# Battery_Pack_BP8.net
KiCad netlist of a schematic drawn in Altium Designer
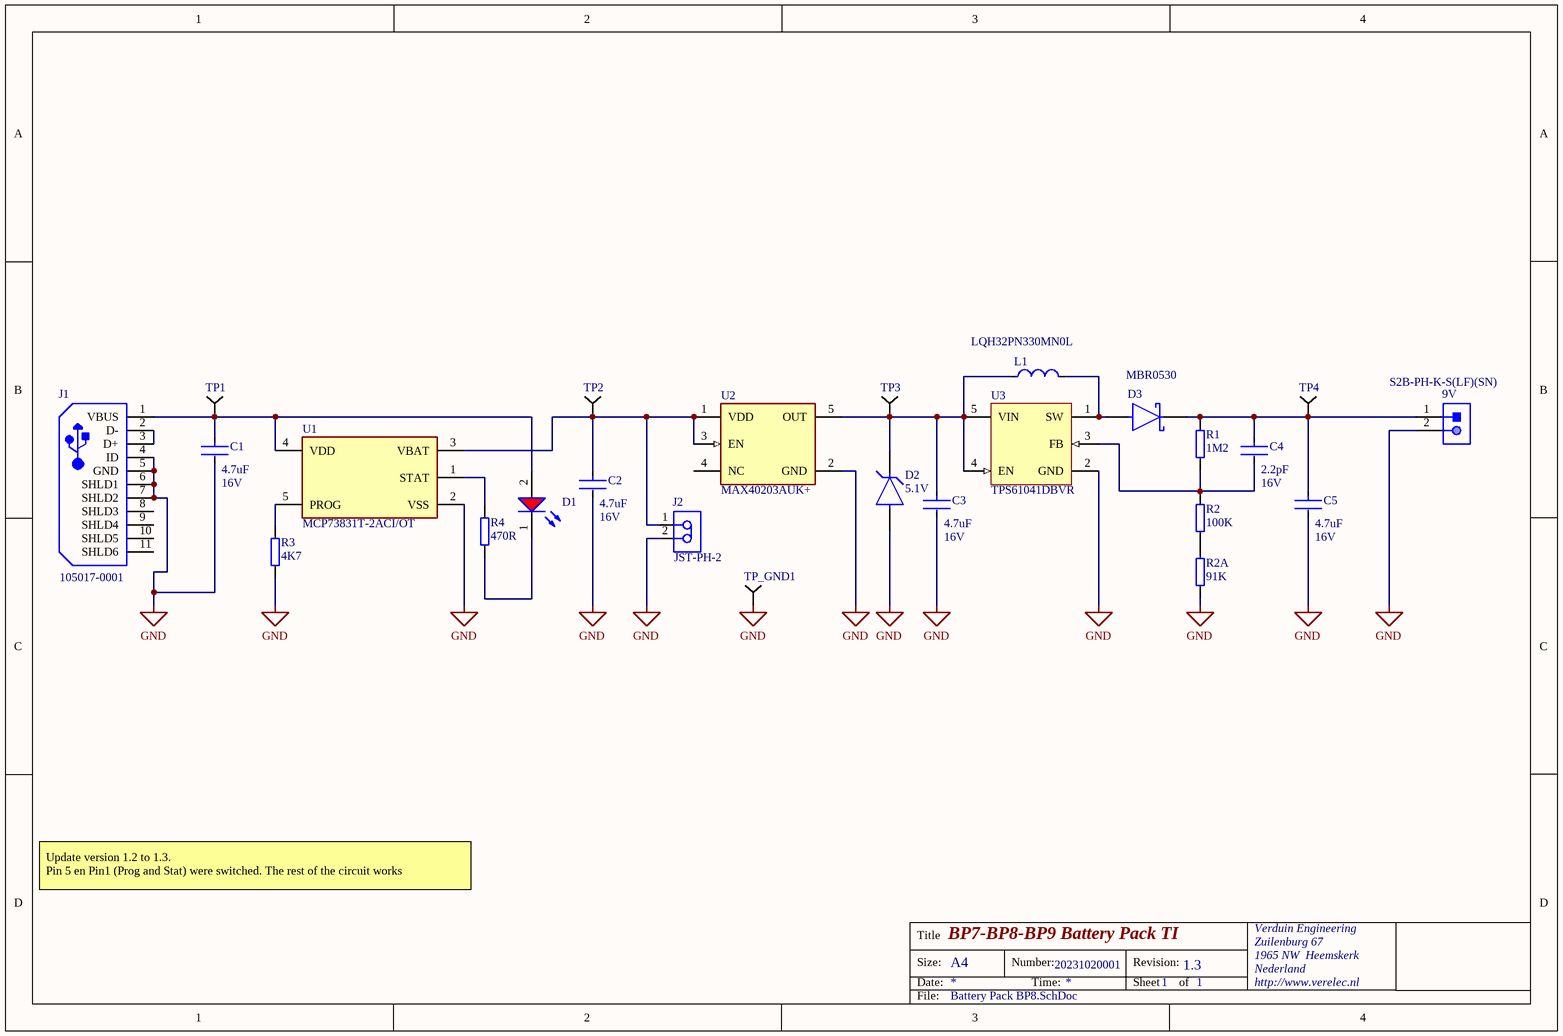
[diagram p0: Battery Pack BP8.SchDoc]

(export (version "E")
  (design (tool "Eeschema 10.0.6"))
  (components
    (comp (ref "9V")
      (value "S2B-PH-K-S(LF)(SN)")
      (footprint "JST-S2B-PH-K-S_V")
      (fields (field (name "TOLERANCE") "20%"))
      (libsource (lib "Altium Content Vault") (part "CN-1P-M-R2"))
    )
    (comp (ref "C1")
      (value "GCM21BR71C475KA73K")
      (footprint "FP-0805-L_2_01_0_2-W_1_25-MFG")
      (description "General Purpose Ceramic Capacitor, 0805, 4.7uF, 10%, X7R, 15%, 16V")
      (fields
        (field (name "VOLTAGE RATING") "16V")
        (field (name "VOLTAGE") "10V")
        (field (name "TOLERANCE") "10%")
        (field (name "CAPACITANCE") "4.7uF")
      )
      (libsource (lib "Altium Content Vault") (part "02cd4be3c70576c341d710602a673aa"))
    )
    (comp (ref "C2")
      (value "GCM21BR71C475KA73K")
      (footprint "FP-0805-L_2_01_0_2-W_1_25-MFG")
      (description "General Purpose Ceramic Capacitor, 0805, 4.7uF, 10%, X7R, 15%, 16V")
      (fields
        (field (name "VOLTAGE RATING") "16V")
        (field (name "VOLTAGE") "10V")
        (field (name "TOLERANCE") "10%")
        (field (name "CAPACITANCE") "4.7uF")
      )
      (libsource (lib "Altium Content Vault") (part "02cd4be3c70576c341d710602a673aa"))
    )
    (comp (ref "C3")
      (value "GCM21BR71C475KA73K")
      (footprint "FP-0805-L_2_01_0_2-W_1_25-MFG")
      (description "General Purpose Ceramic Capacitor, 0805, 4.7uF, 10%, X7R, 15%, 16V")
      (fields
        (field (name "VOLTAGE RATING") "16V")
        (field (name "VOLTAGE") "10V")
        (field (name "TOLERANCE") "10%")
        (field (name "CAPACITANCE") "4.7uF")
      )
      (libsource (lib "Altium Content Vault") (part "02cd4be3c70576c341d710602a673aa"))
    )
    (comp (ref "C4")
      (value "C0805C229C2GACTU")
      (footprint "FP-0805-L_2_01_0_2-W_1_25-MFG")
      (description "General Purpose Ceramic Capacitor, 0805, 4.7uF, 10%, X7R, 15%, 16V")
      (fields
        (field (name "VOLTAGE RATING") "16V")
        (field (name "VOLTAGE") "10V")
        (field (name "TOLERANCE") "10%")
        (field (name "CAPACITANCE") "2.2pF")
      )
      (libsource (lib "Altium Content Vault") (part "02cd4be3c70576c341d710602a673aa"))
    )
    (comp (ref "C5")
      (value "GCM21BR71C475KA73K")
      (footprint "FP-0805-L_2_01_0_2-W_1_25-MFG")
      (description "General Purpose Ceramic Capacitor, 0805, 4.7uF, 10%, X7R, 15%, 16V")
      (fields
        (field (name "VOLTAGE RATING") "16V")
        (field (name "VOLTAGE") "10V")
        (field (name "TOLERANCE") "10%")
        (field (name "CAPACITANCE") "4.7uF")
      )
      (libsource (lib "Altium Content Vault") (part "02cd4be3c70576c341d710602a673aa"))
    )
    (comp (ref "D1")
      (value "150080RS75000")
      (footprint "WL-SMCW_0805_150080xx75000")
      (libsource (lib "Altium Content Vault") (part "LED_Red_2A-1K"))
    )
    (comp (ref "D2")
      (value "BZT52C5V1-7-F")
      (footprint "FP-SOD123-MFG")
      (description "DIODE ZENER 5.1V 500MW SOD123")
      (fields
        (field (name "OCTOPART") "https://octopart.com/bzt52c5v1-7-f-diodes+inc.-326718")
        (field (name "NOM ZENER VOLTAGE") "5.1V")
        (field (name "MANUFACTURER") "Diodes Incorporated")
      )
      (libsource (lib "Altium Content Vault") (part "f813f71cba58e380607f5dd3caf9714"))
    )
    (comp (ref "D3")
      (value "MBR0530")
      (footprint "FP-425-04-MFG")
      (description "DIODE SCHOTTKY 30V 500MA SOD123")
      (libsource (lib "Altium Content Vault") (part "1d6ec82d83fb6aee721767c19dac4b9"))
    )
    (comp (ref "J1")
      (value "105017-0001")
      (footprint "USB-MICRO-B_V")
      (fields (field (name "MANUFACTURER") "Molex"))
      (libsource (lib "Altium Content Vault") (part "USB-5-6SHLD"))
    )
    (comp (ref "J2")
      (value "JST-PH-2")
      (footprint "JST-B2B-PH-K-S_V")
      (description "Connector Header, PH Series, 2 Position, 2.00mm, Through Hole, Press-Fit, Solder, Natural")
      (fields (field (name "Comment") "B2BPHKSLFSN"))
      (libsource (lib "NicoVerduin_Workspace") (part "CN-2P-F-QF2"))
    )
    (comp (ref "L1")
      (value "LQH32PN330MN0L")
      (footprint "FP-LQH32PB_N0-MFG")
      (description "Wire Wound Ferrite Inductor for Power Lines 33μH ±20% 1.38Ω 390mA 1210")
      (fields (field (name "TOLERANCE") "20%"))
      (libsource (lib "Altium Content Vault") (part "725321dda6339637d4d059423bc1c3c"))
    )
    (comp (ref "R1")
      (value "1M2")
      (footprint "RES0805")
      (description "RES SM 0805 NC")
      (fields (field (name "PART NUMBER") "RES-SM-0805-NC") (field (name "MANUFACTURER") "GENERIC"))
      (libsource (lib "electronpowered") (part "RES"))
    )
    (comp (ref "R2")
      (value "100K")
      (footprint "RES0805")
      (description "RES SM 0805 NC")
      (fields (field (name "PART NUMBER") "CRCW0805100KFKEA") (field (name "MANUFACTURER") "Vishay"))
      (libsource (lib "electronpowered") (part "RES"))
    )
    (comp (ref "R2A")
      (value "91K")
      (footprint "RES0805")
      (description "RES SM 0805 NC")
      (fields (field (name "PART NUMBER") "CRCW080591K0FKEA") (field (name "MANUFACTURER") "GENERIC"))
      (libsource (lib "electronpowered") (part "RES"))
    )
    (comp (ref "R3")
      (value "4K7")
      (footprint "RES0805")
      (description "RES SM 0805 NC")
      (fields (field (name "PART NUMBER") "RES-SM-0805-NC") (field (name "MANUFACTURER") "GENERIC"))
      (libsource (lib "electronpowered") (part "RES"))
    )
    (comp (ref "R4")
      (value "470R")
      (footprint "RES0805")
      (description "RES SM 0805 NC")
      (fields (field (name "PART NUMBER") "RES-SM-0805-NC") (field (name "MANUFACTURER") "GENERIC"))
      (libsource (lib "electronpowered") (part "RES"))
    )
    (comp (ref "TP1")
      (value "TESTPOINT")
      (footprint "TP-TOP")
      (libsource (lib "NicoVerduin_Workspace") (part "TP-TOP"))
    )
    (comp (ref "TP2")
      (value "TESTPOINT")
      (footprint "TP-TOP")
      (libsource (lib "NicoVerduin_Workspace") (part "TP-TOP"))
    )
    (comp (ref "TP3")
      (value "TESTPOINT")
      (footprint "TP-TOP")
      (libsource (lib "NicoVerduin_Workspace") (part "TP-TOP"))
    )
    (comp (ref "TP4")
      (value "TESTPOINT")
      (footprint "TP-TOP")
      (libsource (lib "NicoVerduin_Workspace") (part "TP-TOP"))
    )
    (comp (ref "TP_GND1")
      (value "TESTPOINT")
      (footprint "TP-TOP")
      (libsource (lib "NicoVerduin_Workspace") (part "TP-TOP"))
    )
    (comp (ref "U1")
      (value "MCP73831T-2ACI/OT")
      (footprint "SOT23-5")
      (description "Power Supply Support Circuit, Adjustable, 1 Channel, PDSO5")
      (libsource (lib "NicoVerduin_Workspace") (part "61f5a3bb3429d9e0caadea342aa3b19"))
    )
    (comp (ref "U2")
      (value "MAX40203AUK+")
      (footprint "FP-U5-2-MFG")
      (description "IC IDEAL DIODE")
      (fields
        (field (name "MANUFACTURER") "Maxim Integrated")
        (field (name "OCTOPART") "https://octopart.com/max40203auk%2B-maxim+integrated-97007183")
      )
      (libsource (lib "Altium Content Vault") (part "d6b982f9a5baa4355a21b5b266d1e6c"))
    )
    (comp (ref "U3")
      (value "TPS61041DBVR")
      (footprint "DBV0005A_M")
      (fields (field (name "MANUFACTURER") "Texas Instruments"))
      (libsource (lib "Altium Content Vault") (part "TI-TPS61041DBV5"))
    )
  )
  (nets
    (net (code "1") (name "GND") (class "Default")
      (node (ref "9V") (pin "2") (pinfunction "2_2") (pintype "passive"))
      (node (ref "C1") (pin "2") (pinfunction "2_2") (pintype "passive"))
      (node (ref "C2") (pin "2") (pinfunction "2_2") (pintype "passive"))
      (node (ref "C3") (pin "2") (pinfunction "2_2") (pintype "passive"))
      (node (ref "C5") (pin "2") (pinfunction "2_2") (pintype "passive"))
      (node (ref "D2") (pin "2") (pinfunction "A_2") (pintype "passive"))
      (node (ref "J1") (pin "4") (pinfunction "ID_4") (pintype "passive"))
      (node (ref "J1") (pin "5") (pinfunction "GND_5") (pintype "passive"))
      (node (ref "J1") (pin "6") (pinfunction "SHLD1_6") (pintype "passive"))
      (node (ref "J1") (pin "7") (pinfunction "SHLD2_7") (pintype "passive"))
      (node (ref "J2") (pin "2") (pinfunction "2_2") (pintype "passive"))
      (node (ref "R2A") (pin "1") (pinfunction "1_1") (pintype "passive"))
      (node (ref "R3") (pin "1") (pinfunction "1_1") (pintype "passive"))
      (node (ref "TP_GND1") (pin "0") (pinfunction "0_0") (pintype "passive"))
      (node (ref "U1") (pin "2") (pinfunction "VSS_2") (pintype "power_in"))
      (node (ref "U2") (pin "2") (pinfunction "GND_2") (pintype "power_in"))
      (node (ref "U3") (pin "2") (pinfunction "GND_2") (pintype "power_in"))
    )
    (net (code "2") (name "Net-(D1-A)") (class "Default")
      (node (ref "C1") (pin "1") (pinfunction "1_1") (pintype "passive"))
      (node (ref "D1") (pin "2") (pinfunction "A_2") (pintype "passive"))
      (node (ref "J1") (pin "1") (pinfunction "VBUS_1") (pintype "passive"))
      (node (ref "TP1") (pin "0") (pinfunction "0_0") (pintype "passive"))
      (node (ref "U1") (pin "4") (pinfunction "VDD_4") (pintype "power_in"))
    )
    (net (code "3") (name "Net-(D1-K)") (class "Default")
      (node (ref "D1") (pin "1") (pinfunction "K_1") (pintype "passive"))
      (node (ref "R4") (pin "1") (pinfunction "1_1") (pintype "passive"))
    )
    (net (code "4") (name "Net-(D2-C)") (class "Default")
      (node (ref "C3") (pin "1") (pinfunction "1_1") (pintype "passive"))
      (node (ref "D2") (pin "1") (pinfunction "C_1") (pintype "passive"))
      (node (ref "L1") (pin "1") (pinfunction "1_1") (pintype "passive"))
      (node (ref "TP3") (pin "0") (pinfunction "0_0") (pintype "passive"))
      (node (ref "U2") (pin "5") (pinfunction "OUT_5") (pintype "power_in"))
      (node (ref "U3") (pin "4") (pinfunction "EN_4") (pintype "input"))
      (node (ref "U3") (pin "5") (pinfunction "VIN_5") (pintype "power_in"))
    )
    (net (code "5") (name "Net-(D3-A)") (class "Default")
      (node (ref "D3") (pin "2") (pinfunction "A_2") (pintype "passive"))
      (node (ref "L1") (pin "2") (pinfunction "2_2") (pintype "passive"))
      (node (ref "U3") (pin "1") (pinfunction "SW_1") (pintype "power_in"))
    )
    (net (code "6") (name "Net-(D3-C)") (class "Default")
      (node (ref "9V") (pin "1") (pinfunction "1_1") (pintype "passive"))
      (node (ref "C4") (pin "1") (pinfunction "1_1") (pintype "passive"))
      (node (ref "C5") (pin "1") (pinfunction "1_1") (pintype "passive"))
      (node (ref "D3") (pin "1") (pinfunction "C_1") (pintype "passive"))
      (node (ref "R1") (pin "2") (pinfunction "2_2") (pintype "passive"))
      (node (ref "TP4") (pin "0") (pinfunction "0_0") (pintype "passive"))
    )
    (net (code "7") (name "Net-(J1-D+)") (class "Default")
      (node (ref "J1") (pin "2") (pinfunction "D-_2") (pintype "passive"))
      (node (ref "J1") (pin "3") (pinfunction "D+_3") (pintype "passive"))
    )
    (net (code "8") (name "Net-(R2-Pad1)") (class "Default")
      (node (ref "R2") (pin "1") (pinfunction "1_1") (pintype "passive"))
      (node (ref "R2A") (pin "2") (pinfunction "2_2") (pintype "passive"))
    )
    (net (code "9") (name "Net-(U1-PROG)") (class "Default")
      (node (ref "R3") (pin "2") (pinfunction "2_2") (pintype "passive"))
      (node (ref "U1") (pin "5") (pinfunction "PROG_5") (pintype "passive"))
    )
    (net (code "10") (name "Net-(U1-STAT)") (class "Default")
      (node (ref "R4") (pin "2") (pinfunction "2_2") (pintype "passive"))
      (node (ref "U1") (pin "1") (pinfunction "STAT_1") (pintype "passive"))
    )
    (net (code "11") (name "Net-(U1-VBAT)") (class "Default")
      (node (ref "C2") (pin "1") (pinfunction "1_1") (pintype "passive"))
      (node (ref "J2") (pin "1") (pinfunction "1_1") (pintype "passive"))
      (node (ref "TP2") (pin "0") (pinfunction "0_0") (pintype "passive"))
      (node (ref "U1") (pin "3") (pinfunction "VBAT_3") (pintype "power_in"))
      (node (ref "U2") (pin "1") (pinfunction "VDD_1") (pintype "power_in"))
      (node (ref "U2") (pin "3") (pinfunction "EN_3") (pintype "input"))
    )
    (net (code "12") (name "Net-(U3-FB)") (class "Default")
      (node (ref "C4") (pin "2") (pinfunction "2_2") (pintype "passive"))
      (node (ref "R1") (pin "1") (pinfunction "1_1") (pintype "passive"))
      (node (ref "R2") (pin "2") (pinfunction "2_2") (pintype "passive"))
      (node (ref "U3") (pin "3") (pinfunction "FB_3") (pintype "input"))
    )
    (net (code "13") (name "unconnected-(J1-SHLD3-Pad8)") (class "Default")
      (node (ref "J1") (pin "8") (pinfunction "SHLD3_8") (pintype "passive"))
    )
    (net (code "14") (name "unconnected-(J1-SHLD4-Pad9)") (class "Default")
      (node (ref "J1") (pin "9") (pinfunction "SHLD4_9") (pintype "passive"))
    )
    (net (code "15") (name "unconnected-(J1-SHLD5-Pad10)") (class "Default")
      (node (ref "J1") (pin "10") (pinfunction "SHLD5_10") (pintype "passive"))
    )
    (net (code "16") (name "unconnected-(J1-SHLD6-Pad11)") (class "Default")
      (node (ref "J1") (pin "11") (pinfunction "SHLD6_11") (pintype "passive"))
    )
    (net (code "17") (name "unconnected-(U2-NC-Pad4)") (class "Default")
      (node (ref "U2") (pin "4") (pinfunction "NC_4") (pintype "passive"))
    )
  )
)
